# stepper_carriers.net
KiCad netlist of a schematic drawn in EAGLE
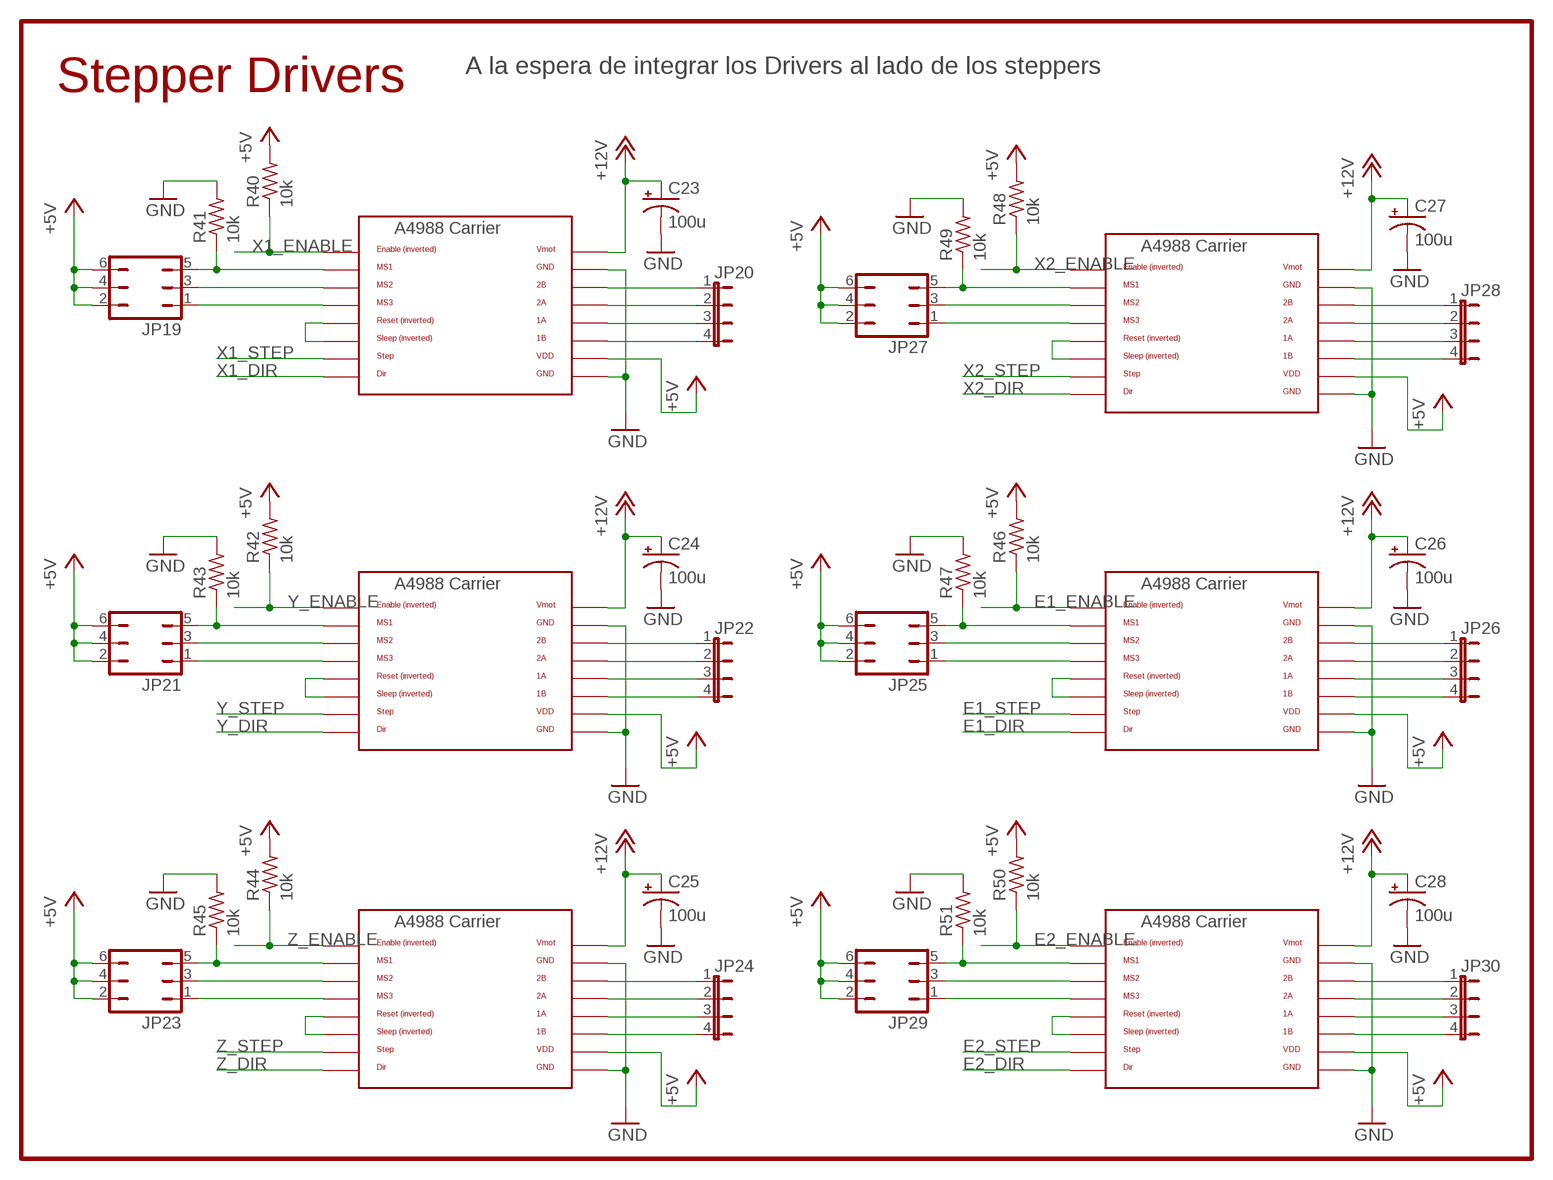
[diagram p0: schematic, sheet 1]

(export (version "E")
  (design (tool "Eeschema 10.0.6"))
  (components
    (comp (ref "C23")
      (value "100u")
      (footprint "eagle-import:140CLH-1010")
      (libsource (lib "eagle-import") (part "CPOL-US140CLH-1010"))
    )
    (comp (ref "C24")
      (value "100u")
      (footprint "eagle-import:140CLH-1010")
      (libsource (lib "eagle-import") (part "CPOL-US140CLH-1010"))
    )
    (comp (ref "C25")
      (value "100u")
      (footprint "eagle-import:140CLH-1010")
      (libsource (lib "eagle-import") (part "CPOL-US140CLH-1010"))
    )
    (comp (ref "C26")
      (value "100u")
      (footprint "eagle-import:140CLH-1010")
      (libsource (lib "eagle-import") (part "CPOL-US140CLH-1010"))
    )
    (comp (ref "C27")
      (value "100u")
      (footprint "eagle-import:140CLH-1010")
      (libsource (lib "eagle-import") (part "CPOL-US140CLH-1010"))
    )
    (comp (ref "C28")
      (value "100u")
      (footprint "eagle-import:140CLH-1010")
      (libsource (lib "eagle-import") (part "CPOL-US140CLH-1010"))
    )
    (comp (ref "JP19")
      (value "JP3Q")
      (footprint "eagle-import:JP3Q")
      (libsource (lib "eagle-import") (part "JP3Q"))
    )
    (comp (ref "JP20")
      (value "JP4E")
      (footprint "eagle-import:JP4")
      (libsource (lib "eagle-import") (part "JP4E"))
    )
    (comp (ref "JP21")
      (value "JP3Q")
      (footprint "eagle-import:JP3Q")
      (libsource (lib "eagle-import") (part "JP3Q"))
    )
    (comp (ref "JP22")
      (value "JP4E")
      (footprint "eagle-import:JP4")
      (libsource (lib "eagle-import") (part "JP4E"))
    )
    (comp (ref "JP23")
      (value "JP3Q")
      (footprint "eagle-import:JP3Q")
      (libsource (lib "eagle-import") (part "JP3Q"))
    )
    (comp (ref "JP24")
      (value "JP4E")
      (footprint "eagle-import:JP4")
      (libsource (lib "eagle-import") (part "JP4E"))
    )
    (comp (ref "JP25")
      (value "JP3Q")
      (footprint "eagle-import:JP3Q")
      (libsource (lib "eagle-import") (part "JP3Q"))
    )
    (comp (ref "JP26")
      (value "JP4E")
      (footprint "eagle-import:JP4")
      (libsource (lib "eagle-import") (part "JP4E"))
    )
    (comp (ref "JP27")
      (value "JP3Q")
      (footprint "eagle-import:JP3Q")
      (libsource (lib "eagle-import") (part "JP3Q"))
    )
    (comp (ref "JP28")
      (value "JP4E")
      (footprint "eagle-import:JP4")
      (libsource (lib "eagle-import") (part "JP4E"))
    )
    (comp (ref "JP29")
      (value "JP3Q")
      (footprint "eagle-import:JP3Q")
      (libsource (lib "eagle-import") (part "JP3Q"))
    )
    (comp (ref "JP30")
      (value "JP4E")
      (footprint "eagle-import:JP4")
      (libsource (lib "eagle-import") (part "JP4E"))
    )
    (comp (ref "R40")
      (value "10k")
      (footprint "eagle-import:R0805")
      (libsource (lib "eagle-import") (part "R-US_R0805"))
    )
    (comp (ref "R41")
      (value "10k")
      (footprint "eagle-import:R0805")
      (libsource (lib "eagle-import") (part "R-US_R0805"))
    )
    (comp (ref "R42")
      (value "10k")
      (footprint "eagle-import:R0805")
      (libsource (lib "eagle-import") (part "R-US_R0805"))
    )
    (comp (ref "R43")
      (value "10k")
      (footprint "eagle-import:R0805")
      (libsource (lib "eagle-import") (part "R-US_R0805"))
    )
    (comp (ref "R44")
      (value "10k")
      (footprint "eagle-import:R0805")
      (libsource (lib "eagle-import") (part "R-US_R0805"))
    )
    (comp (ref "R45")
      (value "10k")
      (footprint "eagle-import:R0805")
      (libsource (lib "eagle-import") (part "R-US_R0805"))
    )
    (comp (ref "R46")
      (value "10k")
      (footprint "eagle-import:R0805")
      (libsource (lib "eagle-import") (part "R-US_R0805"))
    )
    (comp (ref "R47")
      (value "10k")
      (footprint "eagle-import:R0805")
      (libsource (lib "eagle-import") (part "R-US_R0805"))
    )
    (comp (ref "R48")
      (value "10k")
      (footprint "eagle-import:R0805")
      (libsource (lib "eagle-import") (part "R-US_R0805"))
    )
    (comp (ref "R49")
      (value "10k")
      (footprint "eagle-import:R0805")
      (libsource (lib "eagle-import") (part "R-US_R0805"))
    )
    (comp (ref "R50")
      (value "10k")
      (footprint "eagle-import:R0805")
      (libsource (lib "eagle-import") (part "R-US_R0805"))
    )
    (comp (ref "R51")
      (value "10k")
      (footprint "eagle-import:R0805")
      (libsource (lib "eagle-import") (part "R-US_R0805"))
    )
    (comp (ref "U$7")
      (value "A4988BREAKOUT")
      (footprint "eagle-import:A4988BREAKOUT")
      (libsource (lib "eagle-import") (part "A4988BREAKOUT"))
    )
    (comp (ref "U$8")
      (value "A4988BREAKOUT")
      (footprint "eagle-import:A4988BREAKOUT")
      (libsource (lib "eagle-import") (part "A4988BREAKOUT"))
    )
    (comp (ref "U$9")
      (value "A4988BREAKOUT")
      (footprint "eagle-import:A4988BREAKOUT")
      (libsource (lib "eagle-import") (part "A4988BREAKOUT"))
    )
    (comp (ref "U$10")
      (value "A4988BREAKOUT")
      (footprint "eagle-import:A4988BREAKOUT")
      (libsource (lib "eagle-import") (part "A4988BREAKOUT"))
    )
    (comp (ref "U$11")
      (value "A4988BREAKOUT")
      (footprint "eagle-import:A4988BREAKOUT")
      (libsource (lib "eagle-import") (part "A4988BREAKOUT"))
    )
    (comp (ref "U$12")
      (value "A4988BREAKOUT")
      (footprint "eagle-import:A4988BREAKOUT")
      (libsource (lib "eagle-import") (part "A4988BREAKOUT"))
    )
  )
  (nets
    (net (code "1") (name "+5V") (class "Default")
      (node (ref "JP19") (pin "2") (pinfunction "2_2") (pintype "passive"))
      (node (ref "JP19") (pin "4") (pinfunction "4_4") (pintype "passive"))
      (node (ref "JP19") (pin "6") (pinfunction "6_6") (pintype "passive"))
      (node (ref "JP21") (pin "2") (pinfunction "2_2") (pintype "passive"))
      (node (ref "JP21") (pin "4") (pinfunction "4_4") (pintype "passive"))
      (node (ref "JP21") (pin "6") (pinfunction "6_6") (pintype "passive"))
      (node (ref "JP23") (pin "2") (pinfunction "2_2") (pintype "passive"))
      (node (ref "JP23") (pin "4") (pinfunction "4_4") (pintype "passive"))
      (node (ref "JP23") (pin "6") (pinfunction "6_6") (pintype "passive"))
      (node (ref "JP25") (pin "2") (pinfunction "2_2") (pintype "passive"))
      (node (ref "JP25") (pin "4") (pinfunction "4_4") (pintype "passive"))
      (node (ref "JP25") (pin "6") (pinfunction "6_6") (pintype "passive"))
      (node (ref "JP27") (pin "2") (pinfunction "2_2") (pintype "passive"))
      (node (ref "JP27") (pin "4") (pinfunction "4_4") (pintype "passive"))
      (node (ref "JP27") (pin "6") (pinfunction "6_6") (pintype "passive"))
      (node (ref "JP29") (pin "2") (pinfunction "2_2") (pintype "passive"))
      (node (ref "JP29") (pin "4") (pinfunction "4_4") (pintype "passive"))
      (node (ref "JP29") (pin "6") (pinfunction "6_6") (pintype "passive"))
      (node (ref "R40") (pin "2") (pinfunction "2_2") (pintype "passive"))
      (node (ref "R42") (pin "2") (pinfunction "2_2") (pintype "passive"))
      (node (ref "R44") (pin "2") (pinfunction "2_2") (pintype "passive"))
      (node (ref "R46") (pin "2") (pinfunction "2_2") (pintype "passive"))
      (node (ref "R48") (pin "2") (pinfunction "2_2") (pintype "passive"))
      (node (ref "R50") (pin "2") (pinfunction "2_2") (pintype "passive"))
      (node (ref "U$10") (pin "VDD") (pinfunction "VDD_VDD") (pintype "power_in"))
      (node (ref "U$11") (pin "VDD") (pinfunction "VDD_VDD") (pintype "power_in"))
      (node (ref "U$12") (pin "VDD") (pinfunction "VDD_VDD") (pintype "power_in"))
      (node (ref "U$7") (pin "VDD") (pinfunction "VDD_VDD") (pintype "power_in"))
      (node (ref "U$8") (pin "VDD") (pinfunction "VDD_VDD") (pintype "power_in"))
      (node (ref "U$9") (pin "VDD") (pinfunction "VDD_VDD") (pintype "power_in"))
    )
    (net (code "2") (name "+12V") (class "Default")
      (node (ref "C23") (pin "+") (pinfunction "+_+") (pintype "passive"))
      (node (ref "C24") (pin "+") (pinfunction "+_+") (pintype "passive"))
      (node (ref "C25") (pin "+") (pinfunction "+_+") (pintype "passive"))
      (node (ref "C26") (pin "+") (pinfunction "+_+") (pintype "passive"))
      (node (ref "C27") (pin "+") (pinfunction "+_+") (pintype "passive"))
      (node (ref "C28") (pin "+") (pinfunction "+_+") (pintype "passive"))
      (node (ref "U$10") (pin "VMOT") (pinfunction "VMOT_VMOT") (pintype "power_in"))
      (node (ref "U$11") (pin "VMOT") (pinfunction "VMOT_VMOT") (pintype "power_in"))
      (node (ref "U$12") (pin "VMOT") (pinfunction "VMOT_VMOT") (pintype "power_in"))
      (node (ref "U$7") (pin "VMOT") (pinfunction "VMOT_VMOT") (pintype "power_in"))
      (node (ref "U$8") (pin "VMOT") (pinfunction "VMOT_VMOT") (pintype "power_in"))
      (node (ref "U$9") (pin "VMOT") (pinfunction "VMOT_VMOT") (pintype "power_in"))
    )
    (net (code "3") (name "/E1_DIR") (class "Default")
      (node (ref "U$10") (pin "DIR") (pinfunction "DIR_DIR") (pintype "input"))
    )
    (net (code "4") (name "/E1_ENABLE") (class "Default")
      (node (ref "R46") (pin "1") (pinfunction "1_1") (pintype "passive"))
      (node (ref "U$10") (pin "EN") (pinfunction "EN_EN") (pintype "input"))
    )
    (net (code "5") (name "/E1_STEP") (class "Default")
      (node (ref "U$10") (pin "STEP") (pinfunction "STEP_STEP") (pintype "input"))
    )
    (net (code "6") (name "/E2_DIR") (class "Default")
      (node (ref "U$12") (pin "DIR") (pinfunction "DIR_DIR") (pintype "input"))
    )
    (net (code "7") (name "/E2_ENABLE") (class "Default")
      (node (ref "R50") (pin "1") (pinfunction "1_1") (pintype "passive"))
      (node (ref "U$12") (pin "EN") (pinfunction "EN_EN") (pintype "input"))
    )
    (net (code "8") (name "/E2_STEP") (class "Default")
      (node (ref "U$12") (pin "STEP") (pinfunction "STEP_STEP") (pintype "input"))
    )
    (net (code "9") (name "/X1_DIR") (class "Default")
      (node (ref "U$7") (pin "DIR") (pinfunction "DIR_DIR") (pintype "input"))
    )
    (net (code "10") (name "/X1_ENABLE") (class "Default")
      (node (ref "R40") (pin "1") (pinfunction "1_1") (pintype "passive"))
      (node (ref "U$7") (pin "EN") (pinfunction "EN_EN") (pintype "input"))
    )
    (net (code "11") (name "/X1_STEP") (class "Default")
      (node (ref "U$7") (pin "STEP") (pinfunction "STEP_STEP") (pintype "input"))
    )
    (net (code "12") (name "/X2_DIR") (class "Default")
      (node (ref "U$11") (pin "DIR") (pinfunction "DIR_DIR") (pintype "input"))
    )
    (net (code "13") (name "/X2_ENABLE") (class "Default")
      (node (ref "R48") (pin "1") (pinfunction "1_1") (pintype "passive"))
      (node (ref "U$11") (pin "EN") (pinfunction "EN_EN") (pintype "input"))
    )
    (net (code "14") (name "/X2_STEP") (class "Default")
      (node (ref "U$11") (pin "STEP") (pinfunction "STEP_STEP") (pintype "input"))
    )
    (net (code "15") (name "/Y_DIR") (class "Default")
      (node (ref "U$8") (pin "DIR") (pinfunction "DIR_DIR") (pintype "input"))
    )
    (net (code "16") (name "/Y_ENABLE") (class "Default")
      (node (ref "R42") (pin "1") (pinfunction "1_1") (pintype "passive"))
      (node (ref "U$8") (pin "EN") (pinfunction "EN_EN") (pintype "input"))
    )
    (net (code "17") (name "/Y_STEP") (class "Default")
      (node (ref "U$8") (pin "STEP") (pinfunction "STEP_STEP") (pintype "input"))
    )
    (net (code "18") (name "/Z_DIR") (class "Default")
      (node (ref "U$9") (pin "DIR") (pinfunction "DIR_DIR") (pintype "input"))
    )
    (net (code "19") (name "/Z_ENABLE") (class "Default")
      (node (ref "R44") (pin "1") (pinfunction "1_1") (pintype "passive"))
      (node (ref "U$9") (pin "EN") (pinfunction "EN_EN") (pintype "input"))
    )
    (net (code "20") (name "/Z_STEP") (class "Default")
      (node (ref "U$9") (pin "STEP") (pinfunction "STEP_STEP") (pintype "input"))
    )
    (net (code "21") (name "GND") (class "Default")
      (node (ref "C23") (pin "-") (pinfunction "-_-") (pintype "passive"))
      (node (ref "C24") (pin "-") (pinfunction "-_-") (pintype "passive"))
      (node (ref "C25") (pin "-") (pinfunction "-_-") (pintype "passive"))
      (node (ref "C26") (pin "-") (pinfunction "-_-") (pintype "passive"))
      (node (ref "C27") (pin "-") (pinfunction "-_-") (pintype "passive"))
      (node (ref "C28") (pin "-") (pinfunction "-_-") (pintype "passive"))
      (node (ref "R41") (pin "2") (pinfunction "2_2") (pintype "passive"))
      (node (ref "R43") (pin "2") (pinfunction "2_2") (pintype "passive"))
      (node (ref "R45") (pin "2") (pinfunction "2_2") (pintype "passive"))
      (node (ref "R47") (pin "2") (pinfunction "2_2") (pintype "passive"))
      (node (ref "R49") (pin "2") (pinfunction "2_2") (pintype "passive"))
      (node (ref "R51") (pin "2") (pinfunction "2_2") (pintype "passive"))
      (node (ref "U$10") (pin "GND") (pinfunction "GND_GND") (pintype "power_in"))
      (node (ref "U$10") (pin "GND@0") (pinfunction "GND_GND@0") (pintype "power_in"))
      (node (ref "U$11") (pin "GND") (pinfunction "GND_GND") (pintype "power_in"))
      (node (ref "U$11") (pin "GND@0") (pinfunction "GND_GND@0") (pintype "power_in"))
      (node (ref "U$12") (pin "GND") (pinfunction "GND_GND") (pintype "power_in"))
      (node (ref "U$12") (pin "GND@0") (pinfunction "GND_GND@0") (pintype "power_in"))
      (node (ref "U$7") (pin "GND") (pinfunction "GND_GND") (pintype "power_in"))
      (node (ref "U$7") (pin "GND@0") (pinfunction "GND_GND@0") (pintype "power_in"))
      (node (ref "U$8") (pin "GND") (pinfunction "GND_GND") (pintype "power_in"))
      (node (ref "U$8") (pin "GND@0") (pinfunction "GND_GND@0") (pintype "power_in"))
      (node (ref "U$9") (pin "GND") (pinfunction "GND_GND") (pintype "power_in"))
      (node (ref "U$9") (pin "GND@0") (pinfunction "GND_GND@0") (pintype "power_in"))
    )
    (net (code "22") (name "Net-(JP19-Pad1)") (class "Default")
      (node (ref "JP19") (pin "1") (pinfunction "1_1") (pintype "passive"))
      (node (ref "U$7") (pin "MS3") (pinfunction "MS3_MS3") (pintype "input"))
    )
    (net (code "23") (name "Net-(JP19-Pad3)") (class "Default")
      (node (ref "JP19") (pin "3") (pinfunction "3_3") (pintype "passive"))
      (node (ref "U$7") (pin "MS2") (pinfunction "MS2_MS2") (pintype "input"))
    )
    (net (code "24") (name "Net-(JP19-Pad5)") (class "Default")
      (node (ref "JP19") (pin "5") (pinfunction "5_5") (pintype "passive"))
      (node (ref "R41") (pin "1") (pinfunction "1_1") (pintype "passive"))
      (node (ref "U$7") (pin "MS1") (pinfunction "MS1_MS1") (pintype "input"))
    )
    (net (code "25") (name "Net-(JP20-Pad1)") (class "Default")
      (node (ref "JP20") (pin "1") (pinfunction "1_1") (pintype "passive"))
      (node (ref "U$7") (pin "2B") (pinfunction "2B_2B") (pintype "output"))
    )
    (net (code "26") (name "Net-(JP20-Pad2)") (class "Default")
      (node (ref "JP20") (pin "2") (pinfunction "2_2") (pintype "passive"))
      (node (ref "U$7") (pin "2A") (pinfunction "2A_2A") (pintype "output"))
    )
    (net (code "27") (name "Net-(JP20-Pad3)") (class "Default")
      (node (ref "JP20") (pin "3") (pinfunction "3_3") (pintype "passive"))
      (node (ref "U$7") (pin "1A") (pinfunction "1A_1A") (pintype "output"))
    )
    (net (code "28") (name "Net-(JP20-Pad4)") (class "Default")
      (node (ref "JP20") (pin "4") (pinfunction "4_4") (pintype "passive"))
      (node (ref "U$7") (pin "1B") (pinfunction "1B_1B") (pintype "output"))
    )
    (net (code "29") (name "Net-(JP21-Pad1)") (class "Default")
      (node (ref "JP21") (pin "1") (pinfunction "1_1") (pintype "passive"))
      (node (ref "U$8") (pin "MS3") (pinfunction "MS3_MS3") (pintype "input"))
    )
    (net (code "30") (name "Net-(JP21-Pad3)") (class "Default")
      (node (ref "JP21") (pin "3") (pinfunction "3_3") (pintype "passive"))
      (node (ref "U$8") (pin "MS2") (pinfunction "MS2_MS2") (pintype "input"))
    )
    (net (code "31") (name "Net-(JP21-Pad5)") (class "Default")
      (node (ref "JP21") (pin "5") (pinfunction "5_5") (pintype "passive"))
      (node (ref "R43") (pin "1") (pinfunction "1_1") (pintype "passive"))
      (node (ref "U$8") (pin "MS1") (pinfunction "MS1_MS1") (pintype "input"))
    )
    (net (code "32") (name "Net-(JP22-Pad1)") (class "Default")
      (node (ref "JP22") (pin "1") (pinfunction "1_1") (pintype "passive"))
      (node (ref "U$8") (pin "2B") (pinfunction "2B_2B") (pintype "output"))
    )
    (net (code "33") (name "Net-(JP22-Pad2)") (class "Default")
      (node (ref "JP22") (pin "2") (pinfunction "2_2") (pintype "passive"))
      (node (ref "U$8") (pin "2A") (pinfunction "2A_2A") (pintype "output"))
    )
    (net (code "34") (name "Net-(JP22-Pad3)") (class "Default")
      (node (ref "JP22") (pin "3") (pinfunction "3_3") (pintype "passive"))
      (node (ref "U$8") (pin "1A") (pinfunction "1A_1A") (pintype "output"))
    )
    (net (code "35") (name "Net-(JP22-Pad4)") (class "Default")
      (node (ref "JP22") (pin "4") (pinfunction "4_4") (pintype "passive"))
      (node (ref "U$8") (pin "1B") (pinfunction "1B_1B") (pintype "output"))
    )
    (net (code "36") (name "Net-(JP23-Pad1)") (class "Default")
      (node (ref "JP23") (pin "1") (pinfunction "1_1") (pintype "passive"))
      (node (ref "U$9") (pin "MS3") (pinfunction "MS3_MS3") (pintype "input"))
    )
    (net (code "37") (name "Net-(JP23-Pad3)") (class "Default")
      (node (ref "JP23") (pin "3") (pinfunction "3_3") (pintype "passive"))
      (node (ref "U$9") (pin "MS2") (pinfunction "MS2_MS2") (pintype "input"))
    )
    (net (code "38") (name "Net-(JP23-Pad5)") (class "Default")
      (node (ref "JP23") (pin "5") (pinfunction "5_5") (pintype "passive"))
      (node (ref "R45") (pin "1") (pinfunction "1_1") (pintype "passive"))
      (node (ref "U$9") (pin "MS1") (pinfunction "MS1_MS1") (pintype "input"))
    )
    (net (code "39") (name "Net-(JP24-Pad1)") (class "Default")
      (node (ref "JP24") (pin "1") (pinfunction "1_1") (pintype "passive"))
      (node (ref "U$9") (pin "2B") (pinfunction "2B_2B") (pintype "output"))
    )
    (net (code "40") (name "Net-(JP24-Pad2)") (class "Default")
      (node (ref "JP24") (pin "2") (pinfunction "2_2") (pintype "passive"))
      (node (ref "U$9") (pin "2A") (pinfunction "2A_2A") (pintype "output"))
    )
    (net (code "41") (name "Net-(JP24-Pad3)") (class "Default")
      (node (ref "JP24") (pin "3") (pinfunction "3_3") (pintype "passive"))
      (node (ref "U$9") (pin "1A") (pinfunction "1A_1A") (pintype "output"))
    )
    (net (code "42") (name "Net-(JP24-Pad4)") (class "Default")
      (node (ref "JP24") (pin "4") (pinfunction "4_4") (pintype "passive"))
      (node (ref "U$9") (pin "1B") (pinfunction "1B_1B") (pintype "output"))
    )
    (net (code "43") (name "Net-(JP25-Pad1)") (class "Default")
      (node (ref "JP25") (pin "1") (pinfunction "1_1") (pintype "passive"))
      (node (ref "U$10") (pin "MS3") (pinfunction "MS3_MS3") (pintype "input"))
    )
    (net (code "44") (name "Net-(JP25-Pad3)") (class "Default")
      (node (ref "JP25") (pin "3") (pinfunction "3_3") (pintype "passive"))
      (node (ref "U$10") (pin "MS2") (pinfunction "MS2_MS2") (pintype "input"))
    )
    (net (code "45") (name "Net-(JP25-Pad5)") (class "Default")
      (node (ref "JP25") (pin "5") (pinfunction "5_5") (pintype "passive"))
      (node (ref "R47") (pin "1") (pinfunction "1_1") (pintype "passive"))
      (node (ref "U$10") (pin "MS1") (pinfunction "MS1_MS1") (pintype "input"))
    )
    (net (code "46") (name "Net-(JP26-Pad1)") (class "Default")
      (node (ref "JP26") (pin "1") (pinfunction "1_1") (pintype "passive"))
      (node (ref "U$10") (pin "2B") (pinfunction "2B_2B") (pintype "output"))
    )
    (net (code "47") (name "Net-(JP26-Pad2)") (class "Default")
      (node (ref "JP26") (pin "2") (pinfunction "2_2") (pintype "passive"))
      (node (ref "U$10") (pin "2A") (pinfunction "2A_2A") (pintype "output"))
    )
    (net (code "48") (name "Net-(JP26-Pad3)") (class "Default")
      (node (ref "JP26") (pin "3") (pinfunction "3_3") (pintype "passive"))
      (node (ref "U$10") (pin "1A") (pinfunction "1A_1A") (pintype "output"))
    )
    (net (code "49") (name "Net-(JP26-Pad4)") (class "Default")
      (node (ref "JP26") (pin "4") (pinfunction "4_4") (pintype "passive"))
      (node (ref "U$10") (pin "1B") (pinfunction "1B_1B") (pintype "output"))
    )
    (net (code "50") (name "Net-(JP27-Pad1)") (class "Default")
      (node (ref "JP27") (pin "1") (pinfunction "1_1") (pintype "passive"))
      (node (ref "U$11") (pin "MS3") (pinfunction "MS3_MS3") (pintype "input"))
    )
    (net (code "51") (name "Net-(JP27-Pad3)") (class "Default")
      (node (ref "JP27") (pin "3") (pinfunction "3_3") (pintype "passive"))
      (node (ref "U$11") (pin "MS2") (pinfunction "MS2_MS2") (pintype "input"))
    )
    (net (code "52") (name "Net-(JP27-Pad5)") (class "Default")
      (node (ref "JP27") (pin "5") (pinfunction "5_5") (pintype "passive"))
      (node (ref "R49") (pin "1") (pinfunction "1_1") (pintype "passive"))
      (node (ref "U$11") (pin "MS1") (pinfunction "MS1_MS1") (pintype "input"))
    )
    (net (code "53") (name "Net-(JP28-Pad1)") (class "Default")
      (node (ref "JP28") (pin "1") (pinfunction "1_1") (pintype "passive"))
      (node (ref "U$11") (pin "2B") (pinfunction "2B_2B") (pintype "output"))
    )
    (net (code "54") (name "Net-(JP28-Pad2)") (class "Default")
      (node (ref "JP28") (pin "2") (pinfunction "2_2") (pintype "passive"))
      (node (ref "U$11") (pin "2A") (pinfunction "2A_2A") (pintype "output"))
    )
    (net (code "55") (name "Net-(JP28-Pad3)") (class "Default")
      (node (ref "JP28") (pin "3") (pinfunction "3_3") (pintype "passive"))
      (node (ref "U$11") (pin "1A") (pinfunction "1A_1A") (pintype "output"))
    )
    (net (code "56") (name "Net-(JP28-Pad4)") (class "Default")
      (node (ref "JP28") (pin "4") (pinfunction "4_4") (pintype "passive"))
      (node (ref "U$11") (pin "1B") (pinfunction "1B_1B") (pintype "output"))
    )
    (net (code "57") (name "Net-(JP29-Pad1)") (class "Default")
      (node (ref "JP29") (pin "1") (pinfunction "1_1") (pintype "passive"))
      (node (ref "U$12") (pin "MS3") (pinfunction "MS3_MS3") (pintype "input"))
    )
    (net (code "58") (name "Net-(JP29-Pad3)") (class "Default")
      (node (ref "JP29") (pin "3") (pinfunction "3_3") (pintype "passive"))
      (node (ref "U$12") (pin "MS2") (pinfunction "MS2_MS2") (pintype "input"))
    )
    (net (code "59") (name "Net-(JP29-Pad5)") (class "Default")
      (node (ref "JP29") (pin "5") (pinfunction "5_5") (pintype "passive"))
      (node (ref "R51") (pin "1") (pinfunction "1_1") (pintype "passive"))
      (node (ref "U$12") (pin "MS1") (pinfunction "MS1_MS1") (pintype "input"))
    )
    (net (code "60") (name "Net-(JP30-Pad1)") (class "Default")
      (node (ref "JP30") (pin "1") (pinfunction "1_1") (pintype "passive"))
      (node (ref "U$12") (pin "2B") (pinfunction "2B_2B") (pintype "output"))
    )
    (net (code "61") (name "Net-(JP30-Pad2)") (class "Default")
      (node (ref "JP30") (pin "2") (pinfunction "2_2") (pintype "passive"))
      (node (ref "U$12") (pin "2A") (pinfunction "2A_2A") (pintype "output"))
    )
    (net (code "62") (name "Net-(JP30-Pad3)") (class "Default")
      (node (ref "JP30") (pin "3") (pinfunction "3_3") (pintype "passive"))
      (node (ref "U$12") (pin "1A") (pinfunction "1A_1A") (pintype "output"))
    )
    (net (code "63") (name "Net-(JP30-Pad4)") (class "Default")
      (node (ref "JP30") (pin "4") (pinfunction "4_4") (pintype "passive"))
      (node (ref "U$12") (pin "1B") (pinfunction "1B_1B") (pintype "output"))
    )
    (net (code "64") (name "Net-(U$7-SLEEP)") (class "Default")
      (node (ref "U$7") (pin "RST") (pinfunction "RST_RST") (pintype "input"))
      (node (ref "U$7") (pin "SLP") (pinfunction "SLEEP_SLP") (pintype "input"))
    )
    (net (code "65") (name "Net-(U$8-SLEEP)") (class "Default")
      (node (ref "U$8") (pin "RST") (pinfunction "RST_RST") (pintype "input"))
      (node (ref "U$8") (pin "SLP") (pinfunction "SLEEP_SLP") (pintype "input"))
    )
    (net (code "66") (name "Net-(U$9-SLEEP)") (class "Default")
      (node (ref "U$9") (pin "RST") (pinfunction "RST_RST") (pintype "input"))
      (node (ref "U$9") (pin "SLP") (pinfunction "SLEEP_SLP") (pintype "input"))
    )
    (net (code "67") (name "Net-(U$10-SLEEP)") (class "Default")
      (node (ref "U$10") (pin "RST") (pinfunction "RST_RST") (pintype "input"))
      (node (ref "U$10") (pin "SLP") (pinfunction "SLEEP_SLP") (pintype "input"))
    )
    (net (code "68") (name "Net-(U$11-SLEEP)") (class "Default")
      (node (ref "U$11") (pin "RST") (pinfunction "RST_RST") (pintype "input"))
      (node (ref "U$11") (pin "SLP") (pinfunction "SLEEP_SLP") (pintype "input"))
    )
    (net (code "69") (name "Net-(U$12-SLEEP)") (class "Default")
      (node (ref "U$12") (pin "RST") (pinfunction "RST_RST") (pintype "input"))
      (node (ref "U$12") (pin "SLP") (pinfunction "SLEEP_SLP") (pintype "input"))
    )
  )
)
